# Autosense-combined.net
KiCad netlist of a schematic drawn in EAGLE
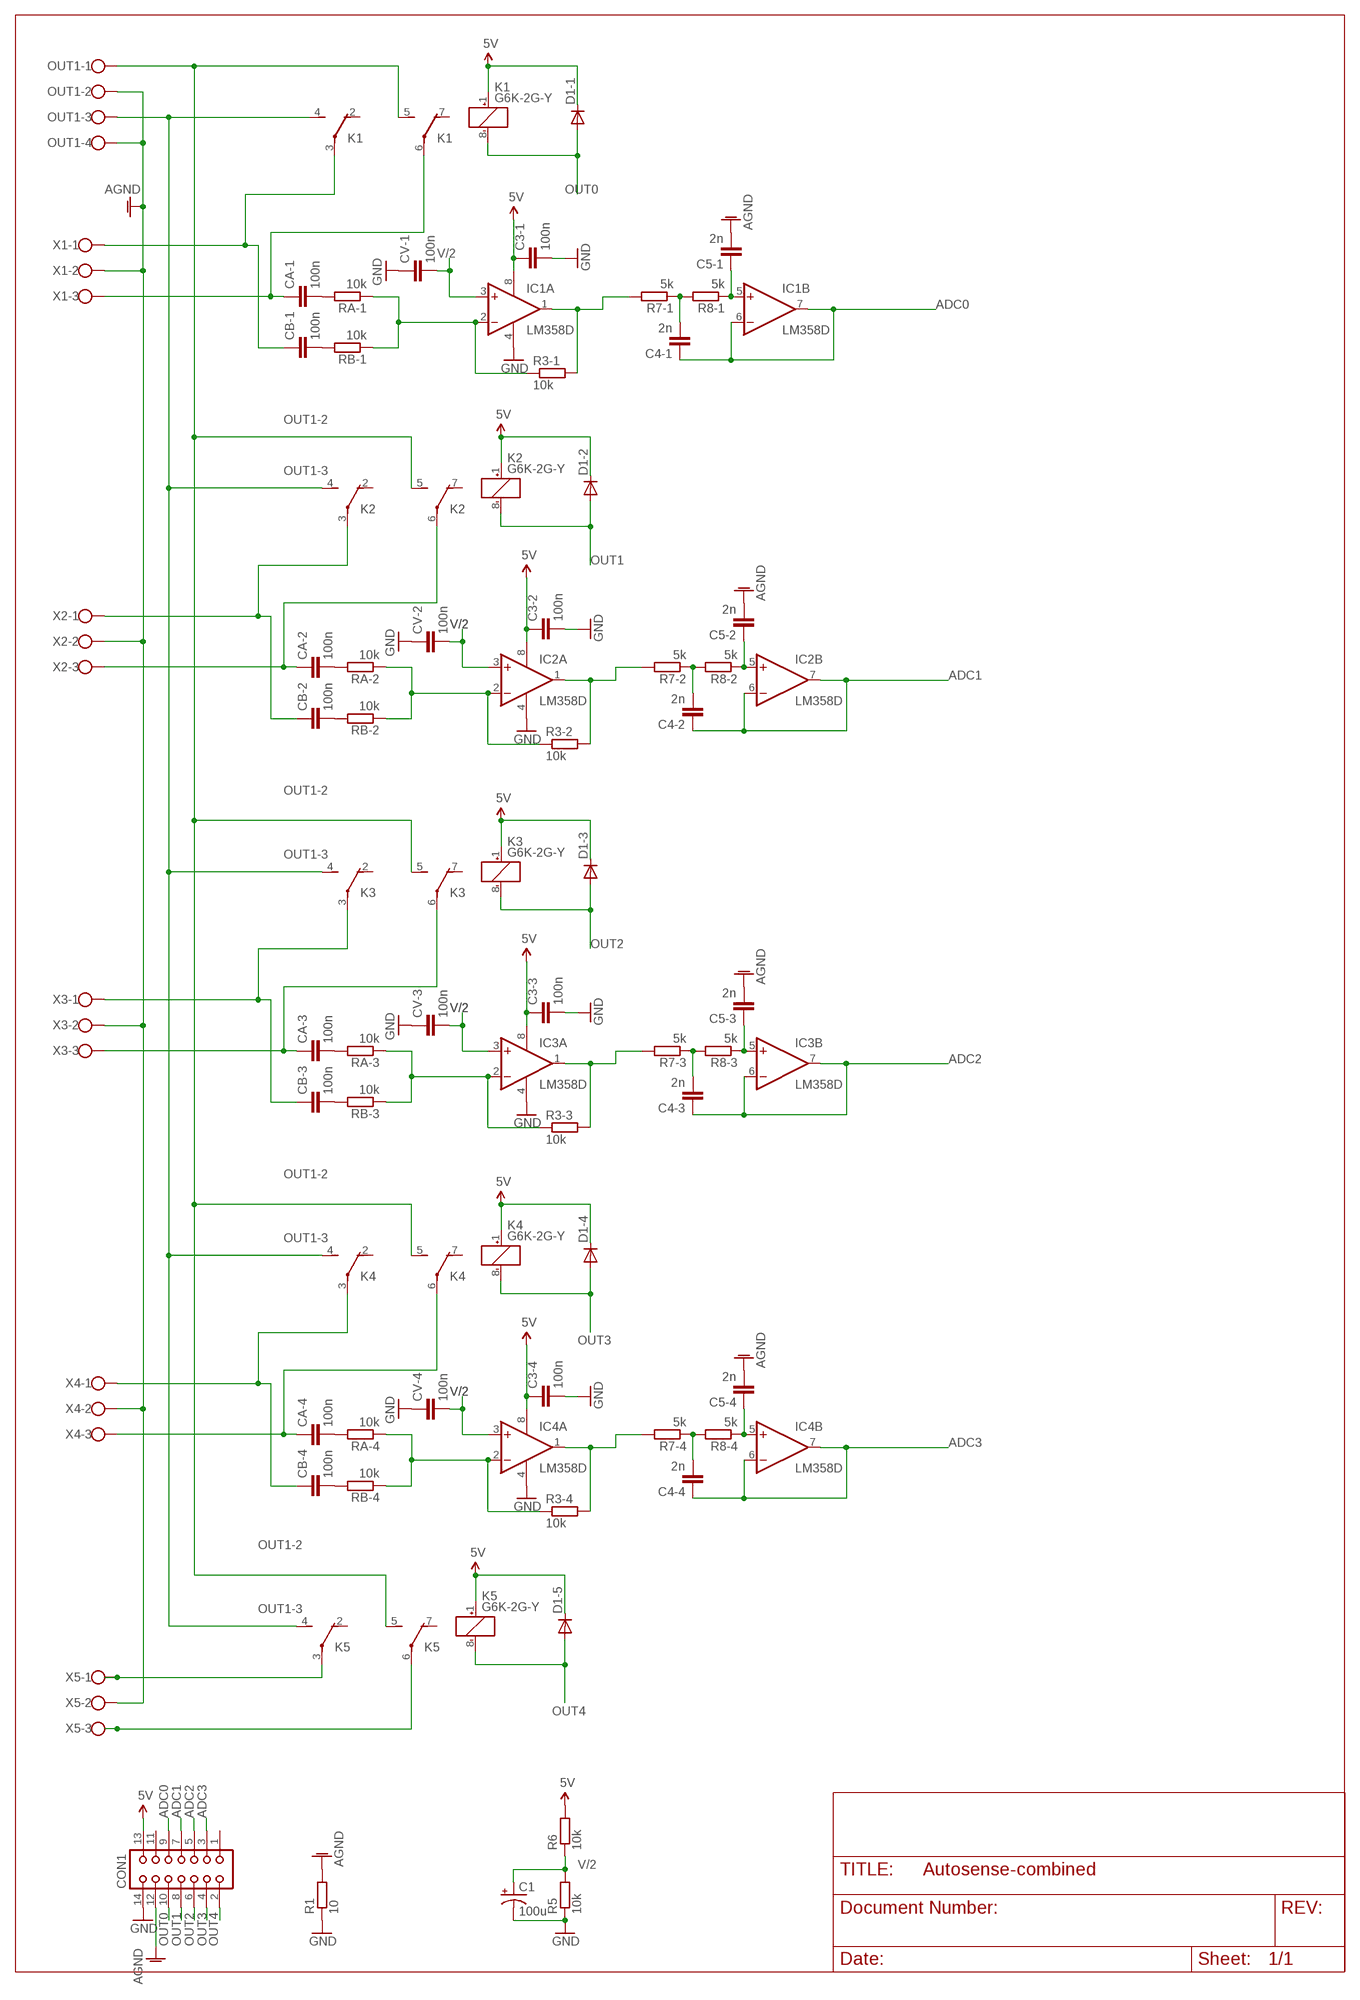
[diagram p0: schematic, sheet 1]

(export (version "E")
  (design (tool "Eeschema 10.0.6"))
  (components
    (comp (ref "C1")
      (value "100u")
      (footprint "eagle-import:CPOL-RADIAL-100UF-25V")
      (libsource (lib "eagle-import") (part "CAP_POLPTH1"))
    )
    (comp (ref "C3-1")
      (value "100n")
      (footprint "eagle-import:C0805")
      (libsource (lib "eagle-import") (part "C-EUC0805"))
    )
    (comp (ref "C3-2")
      (value "100n")
      (footprint "eagle-import:C0805")
      (libsource (lib "eagle-import") (part "C-EUC0805"))
    )
    (comp (ref "C3-3")
      (value "100n")
      (footprint "eagle-import:C0805")
      (libsource (lib "eagle-import") (part "C-EUC0805"))
    )
    (comp (ref "C3-4")
      (value "100n")
      (footprint "eagle-import:C0805")
      (libsource (lib "eagle-import") (part "C-EUC0805"))
    )
    (comp (ref "C4-1")
      (value "2n")
      (footprint "eagle-import:C0805")
      (libsource (lib "eagle-import") (part "C-EUC0805"))
    )
    (comp (ref "C4-2")
      (value "2n")
      (footprint "eagle-import:C0805")
      (libsource (lib "eagle-import") (part "C-EUC0805"))
    )
    (comp (ref "C4-3")
      (value "2n")
      (footprint "eagle-import:C0805")
      (libsource (lib "eagle-import") (part "C-EUC0805"))
    )
    (comp (ref "C4-4")
      (value "2n")
      (footprint "eagle-import:C0805")
      (libsource (lib "eagle-import") (part "C-EUC0805"))
    )
    (comp (ref "C5-1")
      (value "2n")
      (footprint "eagle-import:C0805")
      (libsource (lib "eagle-import") (part "C-EUC0805"))
    )
    (comp (ref "C5-2")
      (value "2n")
      (footprint "eagle-import:C0805")
      (libsource (lib "eagle-import") (part "C-EUC0805"))
    )
    (comp (ref "C5-3")
      (value "2n")
      (footprint "eagle-import:C0805")
      (libsource (lib "eagle-import") (part "C-EUC0805"))
    )
    (comp (ref "C5-4")
      (value "2n")
      (footprint "eagle-import:C0805")
      (libsource (lib "eagle-import") (part "C-EUC0805"))
    )
    (comp (ref "CA-1")
      (value "100n")
      (footprint "eagle-import:C0805")
      (libsource (lib "eagle-import") (part "C-EUC0805"))
    )
    (comp (ref "CA-2")
      (value "100n")
      (footprint "eagle-import:C0805")
      (libsource (lib "eagle-import") (part "C-EUC0805"))
    )
    (comp (ref "CA-3")
      (value "100n")
      (footprint "eagle-import:C0805")
      (libsource (lib "eagle-import") (part "C-EUC0805"))
    )
    (comp (ref "CA-4")
      (value "100n")
      (footprint "eagle-import:C0805")
      (libsource (lib "eagle-import") (part "C-EUC0805"))
    )
    (comp (ref "CB-1")
      (value "100n")
      (footprint "eagle-import:C0805")
      (libsource (lib "eagle-import") (part "C-EUC0805"))
    )
    (comp (ref "CB-2")
      (value "100n")
      (footprint "eagle-import:C0805")
      (libsource (lib "eagle-import") (part "C-EUC0805"))
    )
    (comp (ref "CB-3")
      (value "100n")
      (footprint "eagle-import:C0805")
      (libsource (lib "eagle-import") (part "C-EUC0805"))
    )
    (comp (ref "CB-4")
      (value "100n")
      (footprint "eagle-import:C0805")
      (libsource (lib "eagle-import") (part "C-EUC0805"))
    )
    (comp (ref "CON1")
      (value "CON14L")
      (footprint "eagle-import:CON14L")
      (libsource (lib "eagle-import") (part "CON14L"))
    )
    (comp (ref "CV-1")
      (value "100n")
      (footprint "eagle-import:C0805")
      (libsource (lib "eagle-import") (part "C-EUC0805"))
    )
    (comp (ref "CV-2")
      (value "100n")
      (footprint "eagle-import:C0805")
      (libsource (lib "eagle-import") (part "C-EUC0805"))
    )
    (comp (ref "CV-3")
      (value "100n")
      (footprint "eagle-import:C0805")
      (libsource (lib "eagle-import") (part "C-EUC0805"))
    )
    (comp (ref "CV-4")
      (value "100n")
      (footprint "eagle-import:C0805")
      (libsource (lib "eagle-import") (part "C-EUC0805"))
    )
    (comp (ref "D1-1")
      (value "DIODE-GF1")
      (footprint "eagle-import:GF1")
      (libsource (lib "eagle-import") (part "DIODE-GF1"))
    )
    (comp (ref "D1-2")
      (value "DIODE-GF1")
      (footprint "eagle-import:GF1")
      (libsource (lib "eagle-import") (part "DIODE-GF1"))
    )
    (comp (ref "D1-3")
      (value "DIODE-GF1")
      (footprint "eagle-import:GF1")
      (libsource (lib "eagle-import") (part "DIODE-GF1"))
    )
    (comp (ref "D1-4")
      (value "DIODE-GF1")
      (footprint "eagle-import:GF1")
      (libsource (lib "eagle-import") (part "DIODE-GF1"))
    )
    (comp (ref "D1-5")
      (value "DIODE-GF1")
      (footprint "eagle-import:GF1")
      (libsource (lib "eagle-import") (part "DIODE-GF1"))
    )
    (comp (ref "IC1")
      (value "LM358D")
      (footprint "eagle-import:SO08")
      (libsource (lib "eagle-import") (part "LM358D"))
    )
    (comp (ref "IC2")
      (value "LM358D")
      (footprint "eagle-import:SO08")
      (libsource (lib "eagle-import") (part "LM358D"))
    )
    (comp (ref "IC3")
      (value "LM358D")
      (footprint "eagle-import:SO08")
      (libsource (lib "eagle-import") (part "LM358D"))
    )
    (comp (ref "IC4")
      (value "LM358D")
      (footprint "eagle-import:SO08")
      (libsource (lib "eagle-import") (part "LM358D"))
    )
    (comp (ref "K1")
      (value "G6K-2G-Y")
      (footprint "eagle-import:G6K-2G-Y")
      (libsource (lib "eagle-import") (part "G6K-2G-Y"))
    )
    (comp (ref "K2")
      (value "G6K-2G-Y")
      (footprint "eagle-import:G6K-2G-Y")
      (libsource (lib "eagle-import") (part "G6K-2G-Y"))
    )
    (comp (ref "K3")
      (value "G6K-2G-Y")
      (footprint "eagle-import:G6K-2G-Y")
      (libsource (lib "eagle-import") (part "G6K-2G-Y"))
    )
    (comp (ref "K4")
      (value "G6K-2G-Y")
      (footprint "eagle-import:G6K-2G-Y")
      (libsource (lib "eagle-import") (part "G6K-2G-Y"))
    )
    (comp (ref "K5")
      (value "G6K-2G-Y")
      (footprint "eagle-import:G6K-2G-Y")
      (libsource (lib "eagle-import") (part "G6K-2G-Y"))
    )
    (comp (ref "OUT1")
      (value "W237-4")
      (footprint "eagle-import:W237-4")
      (libsource (lib "eagle-import") (part "W237-4"))
    )
    (comp (ref "R1")
      (value "10")
      (footprint "eagle-import:R1206")
      (libsource (lib "eagle-import") (part "R-EU_R1206"))
    )
    (comp (ref "R3-1")
      (value "10k")
      (footprint "eagle-import:R0805")
      (libsource (lib "eagle-import") (part "resistor_R-EU_R0805"))
    )
    (comp (ref "R3-2")
      (value "10k")
      (footprint "eagle-import:R0805")
      (libsource (lib "eagle-import") (part "resistor_R-EU_R0805"))
    )
    (comp (ref "R3-3")
      (value "10k")
      (footprint "eagle-import:R0805")
      (libsource (lib "eagle-import") (part "resistor_R-EU_R0805"))
    )
    (comp (ref "R3-4")
      (value "10k")
      (footprint "eagle-import:R0805")
      (libsource (lib "eagle-import") (part "resistor_R-EU_R0805"))
    )
    (comp (ref "R5")
      (value "10k")
      (footprint "eagle-import:R0805")
      (libsource (lib "eagle-import") (part "resistor_R-EU_R0805"))
    )
    (comp (ref "R6")
      (value "10k")
      (footprint "eagle-import:R0805")
      (libsource (lib "eagle-import") (part "resistor_R-EU_R0805"))
    )
    (comp (ref "R7-1")
      (value "5k")
      (footprint "eagle-import:R0805")
      (libsource (lib "eagle-import") (part "resistor_R-EU_R0805"))
    )
    (comp (ref "R7-2")
      (value "5k")
      (footprint "eagle-import:R0805")
      (libsource (lib "eagle-import") (part "resistor_R-EU_R0805"))
    )
    (comp (ref "R7-3")
      (value "5k")
      (footprint "eagle-import:R0805")
      (libsource (lib "eagle-import") (part "resistor_R-EU_R0805"))
    )
    (comp (ref "R7-4")
      (value "5k")
      (footprint "eagle-import:R0805")
      (libsource (lib "eagle-import") (part "resistor_R-EU_R0805"))
    )
    (comp (ref "R8-1")
      (value "5k")
      (footprint "eagle-import:R0805")
      (libsource (lib "eagle-import") (part "resistor_R-EU_R0805"))
    )
    (comp (ref "R8-2")
      (value "5k")
      (footprint "eagle-import:R0805")
      (libsource (lib "eagle-import") (part "resistor_R-EU_R0805"))
    )
    (comp (ref "R8-3")
      (value "5k")
      (footprint "eagle-import:R0805")
      (libsource (lib "eagle-import") (part "resistor_R-EU_R0805"))
    )
    (comp (ref "R8-4")
      (value "5k")
      (footprint "eagle-import:R0805")
      (libsource (lib "eagle-import") (part "resistor_R-EU_R0805"))
    )
    (comp (ref "RA-1")
      (value "10k")
      (footprint "eagle-import:R0805")
      (libsource (lib "eagle-import") (part "resistor_R-EU_R0805"))
    )
    (comp (ref "RA-2")
      (value "10k")
      (footprint "eagle-import:R0805")
      (libsource (lib "eagle-import") (part "resistor_R-EU_R0805"))
    )
    (comp (ref "RA-3")
      (value "10k")
      (footprint "eagle-import:R0805")
      (libsource (lib "eagle-import") (part "resistor_R-EU_R0805"))
    )
    (comp (ref "RA-4")
      (value "10k")
      (footprint "eagle-import:R0805")
      (libsource (lib "eagle-import") (part "resistor_R-EU_R0805"))
    )
    (comp (ref "RB-1")
      (value "10k")
      (footprint "eagle-import:M0805")
      (libsource (lib "eagle-import") (part "R-EU_M0805"))
    )
    (comp (ref "RB-2")
      (value "10k")
      (footprint "eagle-import:M0805")
      (libsource (lib "eagle-import") (part "R-EU_M0805"))
    )
    (comp (ref "RB-3")
      (value "10k")
      (footprint "eagle-import:M0805")
      (libsource (lib "eagle-import") (part "R-EU_M0805"))
    )
    (comp (ref "RB-4")
      (value "10k")
      (footprint "eagle-import:M0805")
      (libsource (lib "eagle-import") (part "R-EU_M0805"))
    )
    (comp (ref "X1")
      (value "W237-103")
      (footprint "eagle-import:W237-103")
      (fields (field (name "MPN") "237-103"))
      (libsource (lib "eagle-import") (part "W237-103"))
    )
    (comp (ref "X2")
      (value "W237-103")
      (footprint "eagle-import:W237-103")
      (fields (field (name "MPN") "237-103"))
      (libsource (lib "eagle-import") (part "W237-103"))
    )
    (comp (ref "X3")
      (value "W237-103")
      (footprint "eagle-import:W237-103")
      (fields (field (name "MPN") "237-103"))
      (libsource (lib "eagle-import") (part "W237-103"))
    )
    (comp (ref "X4")
      (value "W237-103")
      (footprint "eagle-import:W237-103")
      (fields (field (name "MPN") "237-103"))
      (libsource (lib "eagle-import") (part "W237-103"))
    )
    (comp (ref "X5")
      (value "W237-103")
      (footprint "eagle-import:W237-103")
      (fields (field (name "MPN") "237-103"))
      (libsource (lib "eagle-import") (part "W237-103"))
    )
  )
  (nets
    (net (code "1") (name "/ADC0") (class "Default")
      (node (ref "C4-1") (pin "1") (pinfunction "1_1") (pintype "passive"))
      (node (ref "CON1") (pin "9") (pinfunction "9_9") (pintype "passive"))
      (node (ref "IC1") (pin "6") (pinfunction "-IN_6") (pintype "input"))
      (node (ref "IC1") (pin "7") (pinfunction "OUT_7") (pintype "output"))
    )
    (net (code "2") (name "/ADC1") (class "Default")
      (node (ref "C4-2") (pin "1") (pinfunction "1_1") (pintype "passive"))
      (node (ref "CON1") (pin "7") (pinfunction "7_7") (pintype "passive"))
      (node (ref "IC2") (pin "6") (pinfunction "-IN_6") (pintype "input"))
      (node (ref "IC2") (pin "7") (pinfunction "OUT_7") (pintype "output"))
    )
    (net (code "3") (name "/ADC2") (class "Default")
      (node (ref "C4-3") (pin "1") (pinfunction "1_1") (pintype "passive"))
      (node (ref "CON1") (pin "5") (pinfunction "5_5") (pintype "passive"))
      (node (ref "IC3") (pin "6") (pinfunction "-IN_6") (pintype "input"))
      (node (ref "IC3") (pin "7") (pinfunction "OUT_7") (pintype "output"))
    )
    (net (code "4") (name "/ADC3") (class "Default")
      (node (ref "C4-4") (pin "1") (pinfunction "1_1") (pintype "passive"))
      (node (ref "CON1") (pin "3") (pinfunction "3_3") (pintype "passive"))
      (node (ref "IC4") (pin "6") (pinfunction "-IN_6") (pintype "input"))
      (node (ref "IC4") (pin "7") (pinfunction "OUT_7") (pintype "output"))
    )
    (net (code "5") (name "/OUT0") (class "Default")
      (node (ref "CON1") (pin "10") (pinfunction "10_10") (pintype "passive"))
      (node (ref "D1-1") (pin "A") (pinfunction "A_A") (pintype "passive"))
      (node (ref "K1") (pin "8") (pinfunction "-_8") (pintype "passive"))
    )
    (net (code "6") (name "/OUT1") (class "Default")
      (node (ref "CON1") (pin "8") (pinfunction "8_8") (pintype "passive"))
      (node (ref "D1-2") (pin "A") (pinfunction "A_A") (pintype "passive"))
      (node (ref "K2") (pin "8") (pinfunction "-_8") (pintype "passive"))
    )
    (net (code "7") (name "/OUT1-2") (class "Default")
      (node (ref "K1") (pin "5") (pinfunction "S_5") (pintype "passive"))
      (node (ref "K2") (pin "5") (pinfunction "S_5") (pintype "passive"))
      (node (ref "K3") (pin "5") (pinfunction "S_5") (pintype "passive"))
      (node (ref "K4") (pin "5") (pinfunction "S_5") (pintype "passive"))
      (node (ref "K5") (pin "5") (pinfunction "S_5") (pintype "passive"))
      (node (ref "OUT1") (pin "1") (pinfunction "KL_1") (pintype "passive"))
    )
    (net (code "8") (name "/OUT1-3") (class "Default")
      (node (ref "K1") (pin "4") (pinfunction "S_4") (pintype "passive"))
      (node (ref "K2") (pin "4") (pinfunction "S_4") (pintype "passive"))
      (node (ref "K3") (pin "4") (pinfunction "S_4") (pintype "passive"))
      (node (ref "K4") (pin "4") (pinfunction "S_4") (pintype "passive"))
      (node (ref "K5") (pin "4") (pinfunction "S_4") (pintype "passive"))
      (node (ref "OUT1") (pin "3") (pinfunction "KL_3") (pintype "passive"))
    )
    (net (code "9") (name "/OUT2") (class "Default")
      (node (ref "CON1") (pin "6") (pinfunction "6_6") (pintype "passive"))
      (node (ref "D1-3") (pin "A") (pinfunction "A_A") (pintype "passive"))
      (node (ref "K3") (pin "8") (pinfunction "-_8") (pintype "passive"))
    )
    (net (code "10") (name "/OUT3") (class "Default")
      (node (ref "CON1") (pin "4") (pinfunction "4_4") (pintype "passive"))
      (node (ref "D1-4") (pin "A") (pinfunction "A_A") (pintype "passive"))
      (node (ref "K4") (pin "8") (pinfunction "-_8") (pintype "passive"))
    )
    (net (code "11") (name "/OUT4") (class "Default")
      (node (ref "CON1") (pin "2") (pinfunction "2_2") (pintype "passive"))
      (node (ref "D1-5") (pin "A") (pinfunction "A_A") (pintype "passive"))
      (node (ref "K5") (pin "8") (pinfunction "-_8") (pintype "passive"))
    )
    (net (code "12") (name "/V{slash}2") (class "Default")
      (node (ref "C1") (pin "1") (pinfunction "+_1") (pintype "passive"))
      (node (ref "CV-1") (pin "2") (pinfunction "2_2") (pintype "passive"))
      (node (ref "CV-2") (pin "2") (pinfunction "2_2") (pintype "passive"))
      (node (ref "CV-3") (pin "2") (pinfunction "2_2") (pintype "passive"))
      (node (ref "CV-4") (pin "2") (pinfunction "2_2") (pintype "passive"))
      (node (ref "IC1") (pin "3") (pinfunction "+IN_3") (pintype "input"))
      (node (ref "IC2") (pin "3") (pinfunction "+IN_3") (pintype "input"))
      (node (ref "IC3") (pin "3") (pinfunction "+IN_3") (pintype "input"))
      (node (ref "IC4") (pin "3") (pinfunction "+IN_3") (pintype "input"))
      (node (ref "R5") (pin "2") (pinfunction "2_2") (pintype "passive"))
      (node (ref "R6") (pin "1") (pinfunction "1_1") (pintype "passive"))
    )
    (net (code "13") (name "5V") (class "Default")
      (node (ref "C3-1") (pin "1") (pinfunction "1_1") (pintype "passive"))
      (node (ref "C3-2") (pin "1") (pinfunction "1_1") (pintype "passive"))
      (node (ref "C3-3") (pin "1") (pinfunction "1_1") (pintype "passive"))
      (node (ref "C3-4") (pin "1") (pinfunction "1_1") (pintype "passive"))
      (node (ref "CON1") (pin "13") (pinfunction "13_13") (pintype "passive"))
      (node (ref "D1-1") (pin "C") (pinfunction "C_C") (pintype "passive"))
      (node (ref "D1-2") (pin "C") (pinfunction "C_C") (pintype "passive"))
      (node (ref "D1-3") (pin "C") (pinfunction "C_C") (pintype "passive"))
      (node (ref "D1-4") (pin "C") (pinfunction "C_C") (pintype "passive"))
      (node (ref "D1-5") (pin "C") (pinfunction "C_C") (pintype "passive"))
      (node (ref "IC1") (pin "8") (pinfunction "V+_8") (pintype "power_in"))
      (node (ref "IC2") (pin "8") (pinfunction "V+_8") (pintype "power_in"))
      (node (ref "IC3") (pin "8") (pinfunction "V+_8") (pintype "power_in"))
      (node (ref "IC4") (pin "8") (pinfunction "V+_8") (pintype "power_in"))
      (node (ref "K1") (pin "1") (pinfunction "+_1") (pintype "passive"))
      (node (ref "K2") (pin "1") (pinfunction "+_1") (pintype "passive"))
      (node (ref "K3") (pin "1") (pinfunction "+_1") (pintype "passive"))
      (node (ref "K4") (pin "1") (pinfunction "+_1") (pintype "passive"))
      (node (ref "K5") (pin "1") (pinfunction "+_1") (pintype "passive"))
      (node (ref "R6") (pin "2") (pinfunction "2_2") (pintype "passive"))
    )
    (net (code "14") (name "AGND") (class "Default")
      (node (ref "C5-1") (pin "2") (pinfunction "2_2") (pintype "passive"))
      (node (ref "C5-2") (pin "2") (pinfunction "2_2") (pintype "passive"))
      (node (ref "C5-3") (pin "2") (pinfunction "2_2") (pintype "passive"))
      (node (ref "C5-4") (pin "2") (pinfunction "2_2") (pintype "passive"))
      (node (ref "CON1") (pin "12") (pinfunction "12_12") (pintype "passive"))
      (node (ref "OUT1") (pin "2") (pinfunction "KL_2") (pintype "passive"))
      (node (ref "OUT1") (pin "4") (pinfunction "KL_4") (pintype "passive"))
      (node (ref "R1") (pin "2") (pinfunction "2_2") (pintype "passive"))
      (node (ref "X1") (pin "2") (pinfunction "KL_2") (pintype "passive"))
      (node (ref "X2") (pin "2") (pinfunction "KL_2") (pintype "passive"))
      (node (ref "X3") (pin "2") (pinfunction "KL_2") (pintype "passive"))
      (node (ref "X4") (pin "2") (pinfunction "KL_2") (pintype "passive"))
      (node (ref "X5") (pin "2") (pinfunction "KL_2") (pintype "passive"))
    )
    (net (code "15") (name "GND") (class "Default")
      (node (ref "C1") (pin "2") (pinfunction "-_2") (pintype "passive"))
      (node (ref "C3-1") (pin "2") (pinfunction "2_2") (pintype "passive"))
      (node (ref "C3-2") (pin "2") (pinfunction "2_2") (pintype "passive"))
      (node (ref "C3-3") (pin "2") (pinfunction "2_2") (pintype "passive"))
      (node (ref "C3-4") (pin "2") (pinfunction "2_2") (pintype "passive"))
      (node (ref "CON1") (pin "14") (pinfunction "14_14") (pintype "passive"))
      (node (ref "CV-1") (pin "1") (pinfunction "1_1") (pintype "passive"))
      (node (ref "CV-2") (pin "1") (pinfunction "1_1") (pintype "passive"))
      (node (ref "CV-3") (pin "1") (pinfunction "1_1") (pintype "passive"))
      (node (ref "CV-4") (pin "1") (pinfunction "1_1") (pintype "passive"))
      (node (ref "IC1") (pin "4") (pinfunction "V-_4") (pintype "power_in"))
      (node (ref "IC2") (pin "4") (pinfunction "V-_4") (pintype "power_in"))
      (node (ref "IC3") (pin "4") (pinfunction "V-_4") (pintype "power_in"))
      (node (ref "IC4") (pin "4") (pinfunction "V-_4") (pintype "power_in"))
      (node (ref "R1") (pin "1") (pinfunction "1_1") (pintype "passive"))
      (node (ref "R5") (pin "1") (pinfunction "1_1") (pintype "passive"))
    )
    (net (code "16") (name "Net-(C4-1-Pad2)") (class "Default")
      (node (ref "C4-1") (pin "2") (pinfunction "2_2") (pintype "passive"))
      (node (ref "R7-1") (pin "1") (pinfunction "1_1") (pintype "passive"))
      (node (ref "R8-1") (pin "2") (pinfunction "2_2") (pintype "passive"))
    )
    (net (code "17") (name "Net-(C4-2-Pad2)") (class "Default")
      (node (ref "C4-2") (pin "2") (pinfunction "2_2") (pintype "passive"))
      (node (ref "R7-2") (pin "1") (pinfunction "1_1") (pintype "passive"))
      (node (ref "R8-2") (pin "2") (pinfunction "2_2") (pintype "passive"))
    )
    (net (code "18") (name "Net-(C4-3-Pad2)") (class "Default")
      (node (ref "C4-3") (pin "2") (pinfunction "2_2") (pintype "passive"))
      (node (ref "R7-3") (pin "1") (pinfunction "1_1") (pintype "passive"))
      (node (ref "R8-3") (pin "2") (pinfunction "2_2") (pintype "passive"))
    )
    (net (code "19") (name "Net-(C4-4-Pad2)") (class "Default")
      (node (ref "C4-4") (pin "2") (pinfunction "2_2") (pintype "passive"))
      (node (ref "R7-4") (pin "1") (pinfunction "1_1") (pintype "passive"))
      (node (ref "R8-4") (pin "2") (pinfunction "2_2") (pintype "passive"))
    )
    (net (code "20") (name "Net-(CA-1-Pad2)") (class "Default")
      (node (ref "CA-1") (pin "2") (pinfunction "2_2") (pintype "passive"))
      (node (ref "RA-1") (pin "2") (pinfunction "2_2") (pintype "passive"))
    )
    (net (code "21") (name "Net-(CA-2-Pad2)") (class "Default")
      (node (ref "CA-2") (pin "2") (pinfunction "2_2") (pintype "passive"))
      (node (ref "RA-2") (pin "2") (pinfunction "2_2") (pintype "passive"))
    )
    (net (code "22") (name "Net-(CA-3-Pad2)") (class "Default")
      (node (ref "CA-3") (pin "2") (pinfunction "2_2") (pintype "passive"))
      (node (ref "RA-3") (pin "2") (pinfunction "2_2") (pintype "passive"))
    )
    (net (code "23") (name "Net-(CA-4-Pad2)") (class "Default")
      (node (ref "CA-4") (pin "2") (pinfunction "2_2") (pintype "passive"))
      (node (ref "RA-4") (pin "2") (pinfunction "2_2") (pintype "passive"))
    )
    (net (code "24") (name "Net-(CB-1-Pad2)") (class "Default")
      (node (ref "CB-1") (pin "2") (pinfunction "2_2") (pintype "passive"))
      (node (ref "RB-1") (pin "2") (pinfunction "2_2") (pintype "passive"))
    )
    (net (code "25") (name "Net-(CB-2-Pad2)") (class "Default")
      (node (ref "CB-2") (pin "2") (pinfunction "2_2") (pintype "passive"))
      (node (ref "RB-2") (pin "2") (pinfunction "2_2") (pintype "passive"))
    )
    (net (code "26") (name "Net-(CB-3-Pad2)") (class "Default")
      (node (ref "CB-3") (pin "2") (pinfunction "2_2") (pintype "passive"))
      (node (ref "RB-3") (pin "2") (pinfunction "2_2") (pintype "passive"))
    )
    (net (code "27") (name "Net-(CB-4-Pad2)") (class "Default")
      (node (ref "CB-4") (pin "2") (pinfunction "2_2") (pintype "passive"))
      (node (ref "RB-4") (pin "2") (pinfunction "2_2") (pintype "passive"))
    )
    (net (code "28") (name "Net-(IC1A--IN)") (class "Default")
      (node (ref "IC1") (pin "2") (pinfunction "-IN_2") (pintype "input"))
      (node (ref "R3-1") (pin "1") (pinfunction "1_1") (pintype "passive"))
      (node (ref "RA-1") (pin "1") (pinfunction "1_1") (pintype "passive"))
      (node (ref "RB-1") (pin "1") (pinfunction "1_1") (pintype "passive"))
    )
    (net (code "29") (name "Net-(IC1A-OUT)") (class "Default")
      (node (ref "IC1") (pin "1") (pinfunction "OUT_1") (pintype "output"))
      (node (ref "R3-1") (pin "2") (pinfunction "2_2") (pintype "passive"))
      (node (ref "R7-1") (pin "2") (pinfunction "2_2") (pintype "passive"))
    )
    (net (code "30") (name "Net-(IC1B-+IN)") (class "Default")
      (node (ref "C5-1") (pin "1") (pinfunction "1_1") (pintype "passive"))
      (node (ref "IC1") (pin "5") (pinfunction "+IN_5") (pintype "input"))
      (node (ref "R8-1") (pin "1") (pinfunction "1_1") (pintype "passive"))
    )
    (net (code "31") (name "Net-(IC2A--IN)") (class "Default")
      (node (ref "IC2") (pin "2") (pinfunction "-IN_2") (pintype "input"))
      (node (ref "R3-2") (pin "1") (pinfunction "1_1") (pintype "passive"))
      (node (ref "RA-2") (pin "1") (pinfunction "1_1") (pintype "passive"))
      (node (ref "RB-2") (pin "1") (pinfunction "1_1") (pintype "passive"))
    )
    (net (code "32") (name "Net-(IC2A-OUT)") (class "Default")
      (node (ref "IC2") (pin "1") (pinfunction "OUT_1") (pintype "output"))
      (node (ref "R3-2") (pin "2") (pinfunction "2_2") (pintype "passive"))
      (node (ref "R7-2") (pin "2") (pinfunction "2_2") (pintype "passive"))
    )
    (net (code "33") (name "Net-(IC2B-+IN)") (class "Default")
      (node (ref "C5-2") (pin "1") (pinfunction "1_1") (pintype "passive"))
      (node (ref "IC2") (pin "5") (pinfunction "+IN_5") (pintype "input"))
      (node (ref "R8-2") (pin "1") (pinfunction "1_1") (pintype "passive"))
    )
    (net (code "34") (name "Net-(IC3A--IN)") (class "Default")
      (node (ref "IC3") (pin "2") (pinfunction "-IN_2") (pintype "input"))
      (node (ref "R3-3") (pin "1") (pinfunction "1_1") (pintype "passive"))
      (node (ref "RA-3") (pin "1") (pinfunction "1_1") (pintype "passive"))
      (node (ref "RB-3") (pin "1") (pinfunction "1_1") (pintype "passive"))
    )
    (net (code "35") (name "Net-(IC3A-OUT)") (class "Default")
      (node (ref "IC3") (pin "1") (pinfunction "OUT_1") (pintype "output"))
      (node (ref "R3-3") (pin "2") (pinfunction "2_2") (pintype "passive"))
      (node (ref "R7-3") (pin "2") (pinfunction "2_2") (pintype "passive"))
    )
    (net (code "36") (name "Net-(IC3B-+IN)") (class "Default")
      (node (ref "C5-3") (pin "1") (pinfunction "1_1") (pintype "passive"))
      (node (ref "IC3") (pin "5") (pinfunction "+IN_5") (pintype "input"))
      (node (ref "R8-3") (pin "1") (pinfunction "1_1") (pintype "passive"))
    )
    (net (code "37") (name "Net-(IC4A--IN)") (class "Default")
      (node (ref "IC4") (pin "2") (pinfunction "-IN_2") (pintype "input"))
      (node (ref "R3-4") (pin "1") (pinfunction "1_1") (pintype "passive"))
      (node (ref "RA-4") (pin "1") (pinfunction "1_1") (pintype "passive"))
      (node (ref "RB-4") (pin "1") (pinfunction "1_1") (pintype "passive"))
    )
    (net (code "38") (name "Net-(IC4A-OUT)") (class "Default")
      (node (ref "IC4") (pin "1") (pinfunction "OUT_1") (pintype "output"))
      (node (ref "R3-4") (pin "2") (pinfunction "2_2") (pintype "passive"))
      (node (ref "R7-4") (pin "2") (pinfunction "2_2") (pintype "passive"))
    )
    (net (code "39") (name "Net-(IC4B-+IN)") (class "Default")
      (node (ref "C5-4") (pin "1") (pinfunction "1_1") (pintype "passive"))
      (node (ref "IC4") (pin "5") (pinfunction "+IN_5") (pintype "input"))
      (node (ref "R8-4") (pin "1") (pinfunction "1_1") (pintype "passive"))
    )
    (net (code "40") (name "Net-(K1B-P)") (class "Default")
      (node (ref "CB-1") (pin "1") (pinfunction "1_1") (pintype "passive"))
      (node (ref "K1") (pin "3") (pinfunction "P_3") (pintype "passive"))
      (node (ref "X1") (pin "1") (pinfunction "KL_1") (pintype "passive"))
    )
    (net (code "41") (name "Net-(K1C-P)") (class "Default")
      (node (ref "CA-1") (pin "1") (pinfunction "1_1") (pintype "passive"))
      (node (ref "K1") (pin "6") (pinfunction "P_6") (pintype "passive"))
      (node (ref "X1") (pin "3") (pinfunction "KL_3") (pintype "passive"))
    )
    (net (code "42") (name "Net-(K2B-P)") (class "Default")
      (node (ref "CB-2") (pin "1") (pinfunction "1_1") (pintype "passive"))
      (node (ref "K2") (pin "3") (pinfunction "P_3") (pintype "passive"))
      (node (ref "X2") (pin "1") (pinfunction "KL_1") (pintype "passive"))
    )
    (net (code "43") (name "Net-(K2C-P)") (class "Default")
      (node (ref "CA-2") (pin "1") (pinfunction "1_1") (pintype "passive"))
      (node (ref "K2") (pin "6") (pinfunction "P_6") (pintype "passive"))
      (node (ref "X2") (pin "3") (pinfunction "KL_3") (pintype "passive"))
    )
    (net (code "44") (name "Net-(K3B-P)") (class "Default")
      (node (ref "CB-3") (pin "1") (pinfunction "1_1") (pintype "passive"))
      (node (ref "K3") (pin "3") (pinfunction "P_3") (pintype "passive"))
      (node (ref "X3") (pin "1") (pinfunction "KL_1") (pintype "passive"))
    )
    (net (code "45") (name "Net-(K3C-P)") (class "Default")
      (node (ref "CA-3") (pin "1") (pinfunction "1_1") (pintype "passive"))
      (node (ref "K3") (pin "6") (pinfunction "P_6") (pintype "passive"))
      (node (ref "X3") (pin "3") (pinfunction "KL_3") (pintype "passive"))
    )
    (net (code "46") (name "Net-(K4B-P)") (class "Default")
      (node (ref "CB-4") (pin "1") (pinfunction "1_1") (pintype "passive"))
      (node (ref "K4") (pin "3") (pinfunction "P_3") (pintype "passive"))
      (node (ref "X4") (pin "1") (pinfunction "KL_1") (pintype "passive"))
    )
    (net (code "47") (name "Net-(K4C-P)") (class "Default")
      (node (ref "CA-4") (pin "1") (pinfunction "1_1") (pintype "passive"))
      (node (ref "K4") (pin "6") (pinfunction "P_6") (pintype "passive"))
      (node (ref "X4") (pin "3") (pinfunction "KL_3") (pintype "passive"))
    )
    (net (code "48") (name "Net-(K5B-P)") (class "Default")
      (node (ref "K5") (pin "3") (pinfunction "P_3") (pintype "passive"))
      (node (ref "X5") (pin "1") (pinfunction "KL_1") (pintype "passive"))
    )
    (net (code "49") (name "Net-(K5C-P)") (class "Default")
      (node (ref "K5") (pin "6") (pinfunction "P_6") (pintype "passive"))
      (node (ref "X5") (pin "3") (pinfunction "KL_3") (pintype "passive"))
    )
    (net (code "50") (name "unconnected-(CON1-Pad1)") (class "Default")
      (node (ref "CON1") (pin "1") (pinfunction "1_1") (pintype "passive"))
    )
    (net (code "51") (name "unconnected-(CON1-Pad11)") (class "Default")
      (node (ref "CON1") (pin "11") (pinfunction "11_11") (pintype "passive"))
    )
    (net (code "52") (name "unconnected-(K1B-O-Pad2)") (class "Default")
      (node (ref "K1") (pin "2") (pinfunction "O_2") (pintype "passive"))
    )
    (net (code "53") (name "unconnected-(K1C-O-Pad7)") (class "Default")
      (node (ref "K1") (pin "7") (pinfunction "O_7") (pintype "passive"))
    )
    (net (code "54") (name "unconnected-(K2B-O-Pad2)") (class "Default")
      (node (ref "K2") (pin "2") (pinfunction "O_2") (pintype "passive"))
    )
    (net (code "55") (name "unconnected-(K2C-O-Pad7)") (class "Default")
      (node (ref "K2") (pin "7") (pinfunction "O_7") (pintype "passive"))
    )
    (net (code "56") (name "unconnected-(K3B-O-Pad2)") (class "Default")
      (node (ref "K3") (pin "2") (pinfunction "O_2") (pintype "passive"))
    )
    (net (code "57") (name "unconnected-(K3C-O-Pad7)") (class "Default")
      (node (ref "K3") (pin "7") (pinfunction "O_7") (pintype "passive"))
    )
    (net (code "58") (name "unconnected-(K4B-O-Pad2)") (class "Default")
      (node (ref "K4") (pin "2") (pinfunction "O_2") (pintype "passive"))
    )
    (net (code "59") (name "unconnected-(K4C-O-Pad7)") (class "Default")
      (node (ref "K4") (pin "7") (pinfunction "O_7") (pintype "passive"))
    )
    (net (code "60") (name "unconnected-(K5B-O-Pad2)") (class "Default")
      (node (ref "K5") (pin "2") (pinfunction "O_2") (pintype "passive"))
    )
    (net (code "61") (name "unconnected-(K5C-O-Pad7)") (class "Default")
      (node (ref "K5") (pin "7") (pinfunction "O_7") (pintype "passive"))
    )
  )
)
